# Arduino_DUE_X_V02d-2Layer.net
KiCad netlist of a schematic drawn in EAGLE
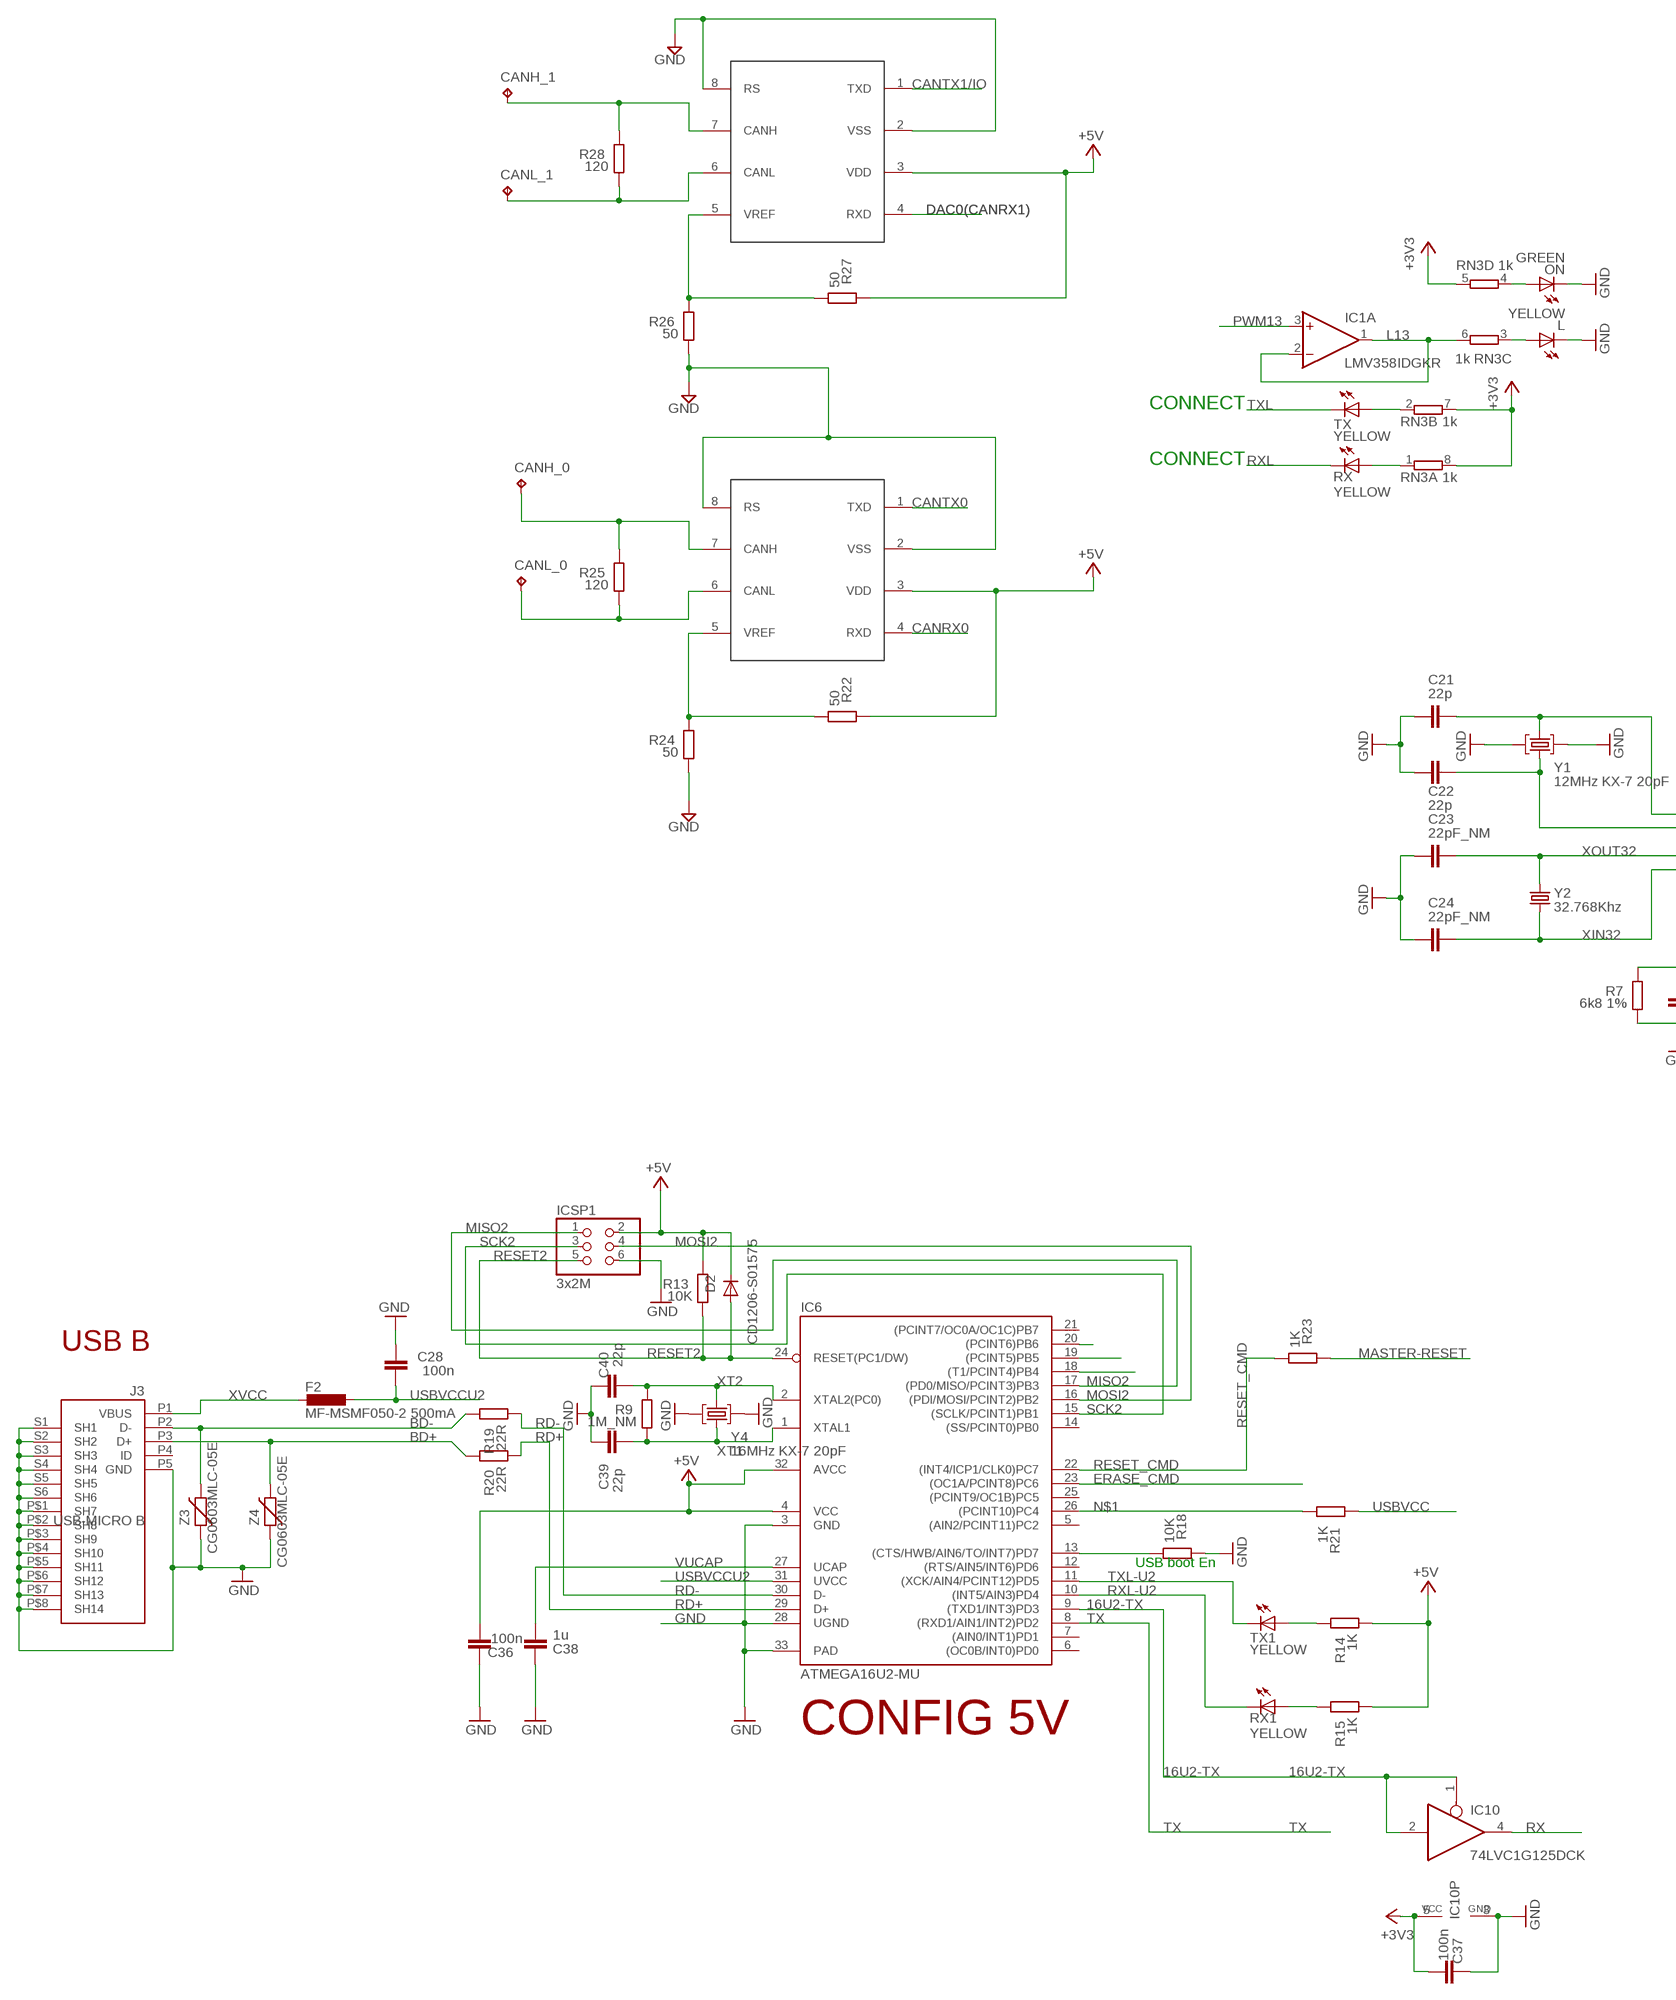
[diagram p0: schematic, sheet 1, part 1 of 2]
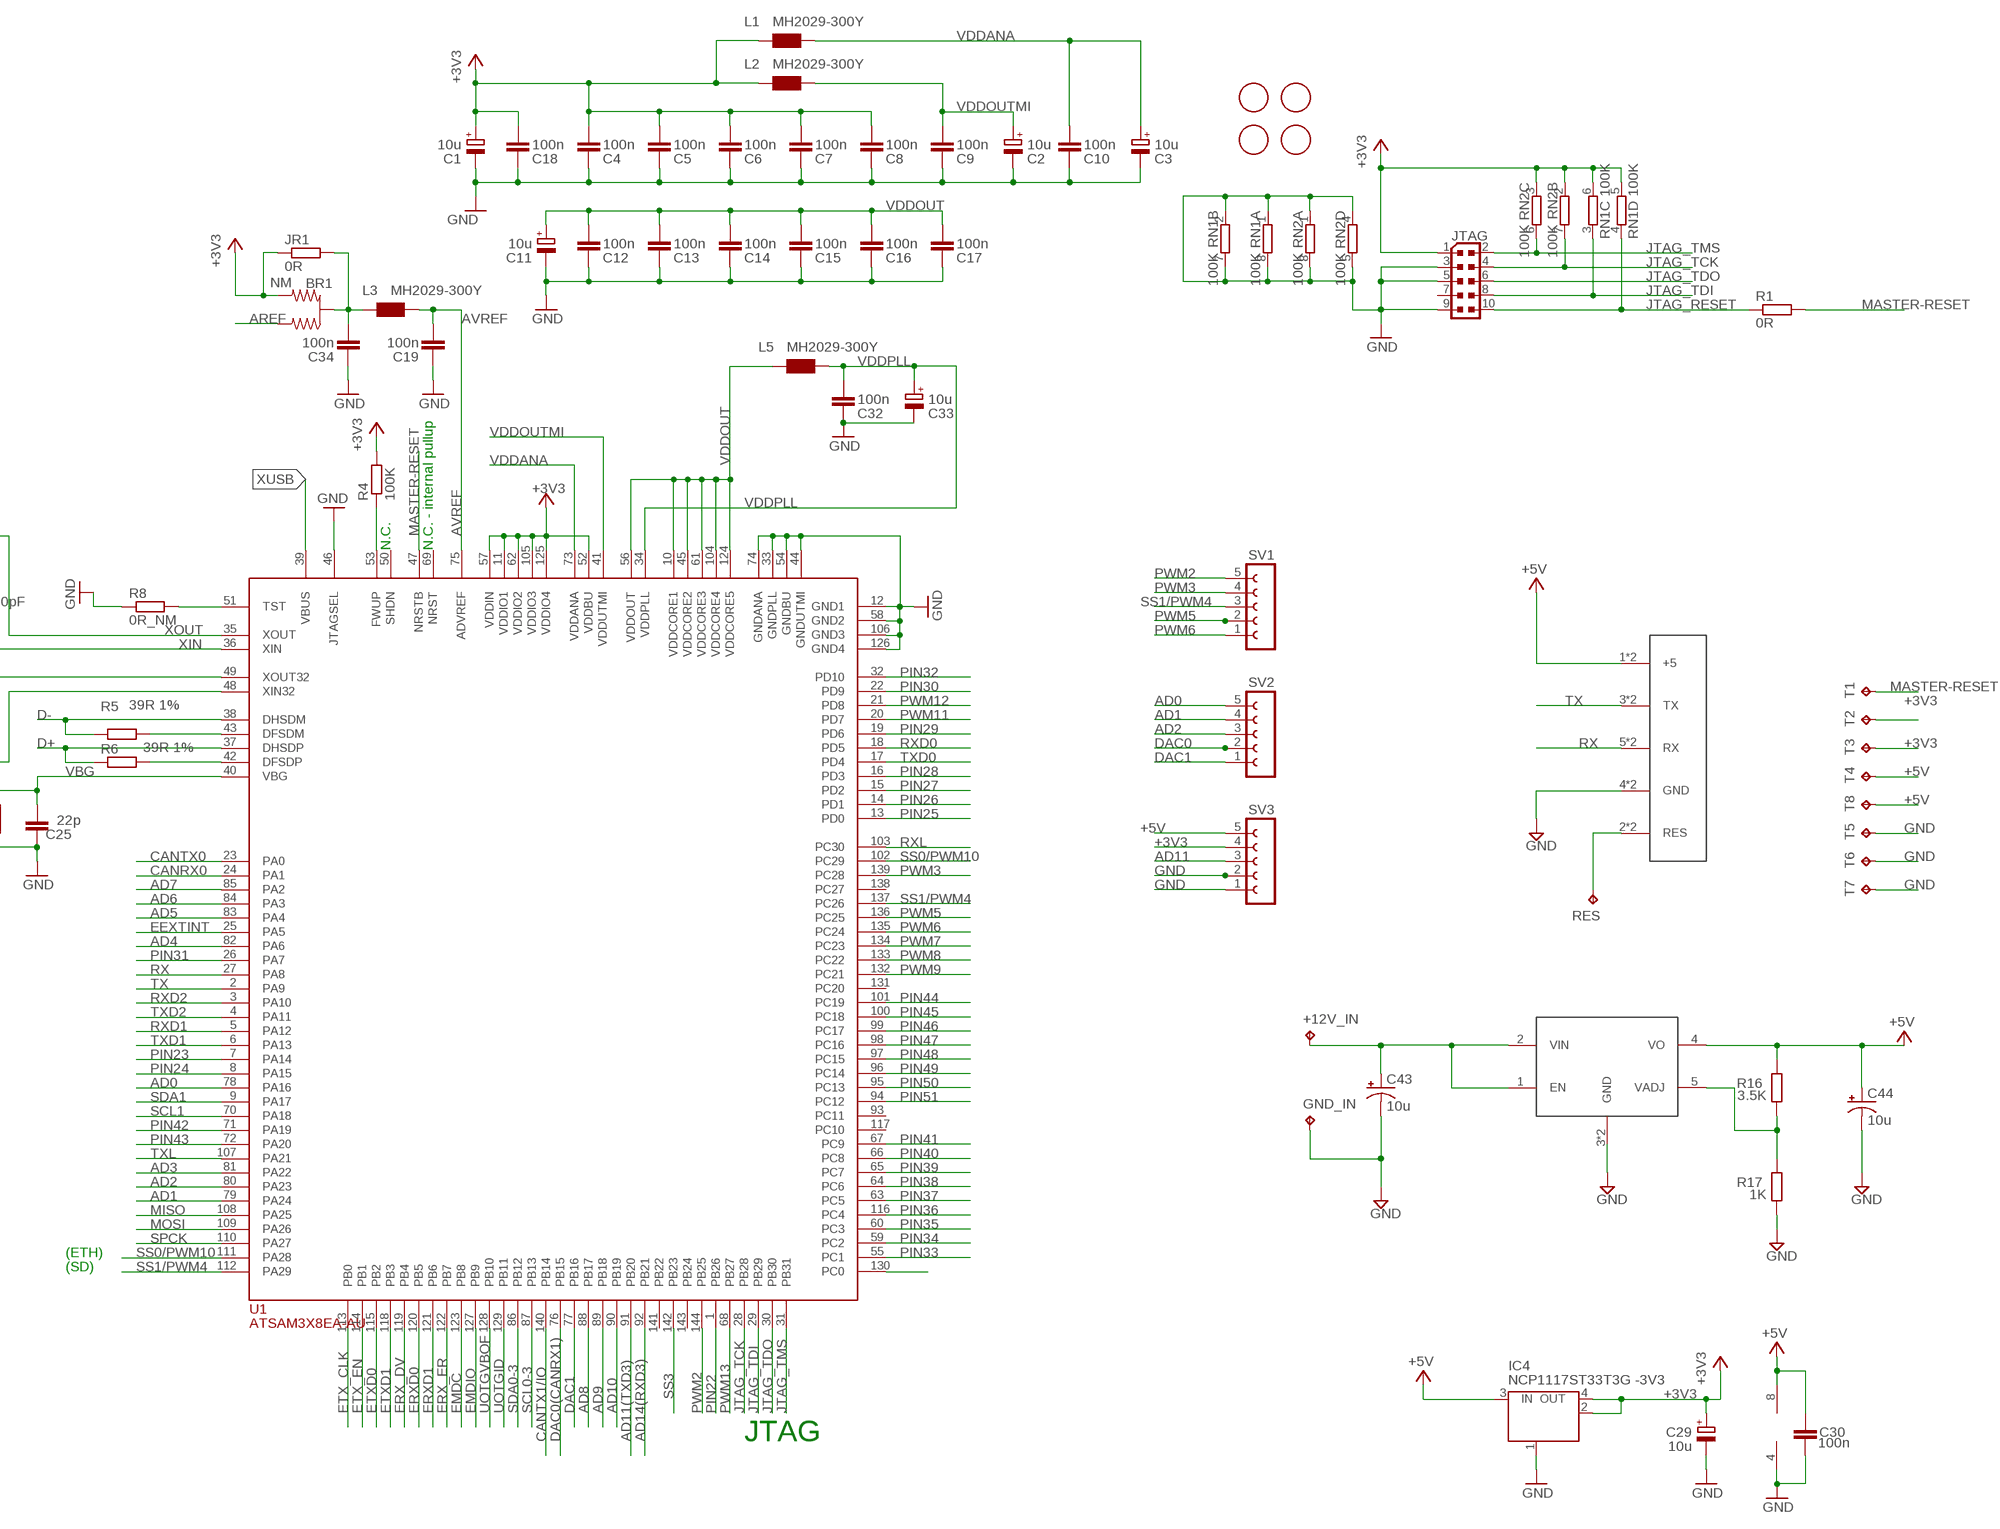
[diagram p1: schematic, sheet 1, part 2 of 2]

(export (version "E")
  (design (tool "Eeschema 10.0.6"))
  (components
    (comp (ref "+12V_IN")
      (value "TPPAD1-13")
      (footprint "eagle-import:P1-13")
      (libsource (lib "eagle-import") (part "TPPAD1-13"))
    )
    (comp (ref "BR1")
      (value "NM")
      (footprint "eagle-import:J0402")
      (libsource (lib "eagle-import") (part "J0402"))
    )
    (comp (ref "C1")
      (value "10u")
      (footprint "eagle-import:SMC_B")
      (libsource (lib "eagle-import") (part "CPOL-EUSMCB"))
    )
    (comp (ref "C2")
      (value "10u")
      (footprint "eagle-import:SMC_B")
      (libsource (lib "eagle-import") (part "CPOL-EUSMCB"))
    )
    (comp (ref "C3")
      (value "10u")
      (footprint "eagle-import:SMC_B")
      (libsource (lib "eagle-import") (part "CPOL-EUSMCB"))
    )
    (comp (ref "C4")
      (value "100n")
      (footprint "eagle-import:C0805")
      (libsource (lib "eagle-import") (part "C-EUC0805"))
    )
    (comp (ref "C5")
      (value "100n")
      (footprint "eagle-import:C0805")
      (libsource (lib "eagle-import") (part "C-EUC0805"))
    )
    (comp (ref "C6")
      (value "100n")
      (footprint "eagle-import:C0805")
      (libsource (lib "eagle-import") (part "C-EUC0805"))
    )
    (comp (ref "C7")
      (value "100n")
      (footprint "eagle-import:C0805")
      (libsource (lib "eagle-import") (part "C-EUC0805"))
    )
    (comp (ref "C8")
      (value "100n")
      (footprint "eagle-import:C0805")
      (libsource (lib "eagle-import") (part "C-EUC0805"))
    )
    (comp (ref "C9")
      (value "100n")
      (footprint "eagle-import:C0805")
      (libsource (lib "eagle-import") (part "C-EUC0805"))
    )
    (comp (ref "C10")
      (value "100n")
      (footprint "eagle-import:C0805")
      (libsource (lib "eagle-import") (part "C-EUC0805"))
    )
    (comp (ref "C11")
      (value "10u")
      (footprint "eagle-import:SMC_B")
      (libsource (lib "eagle-import") (part "CPOL-EUSMCB"))
    )
    (comp (ref "C12")
      (value "100n")
      (footprint "eagle-import:C0805")
      (libsource (lib "eagle-import") (part "C-EUC0805"))
    )
    (comp (ref "C13")
      (value "100n")
      (footprint "eagle-import:C0805")
      (libsource (lib "eagle-import") (part "C-EUC0805"))
    )
    (comp (ref "C14")
      (value "100n")
      (footprint "eagle-import:C0805")
      (libsource (lib "eagle-import") (part "C-EUC0805"))
    )
    (comp (ref "C15")
      (value "100n")
      (footprint "eagle-import:C0805")
      (libsource (lib "eagle-import") (part "C-EUC0805"))
    )
    (comp (ref "C16")
      (value "100n")
      (footprint "eagle-import:C0805")
      (libsource (lib "eagle-import") (part "C-EUC0805"))
    )
    (comp (ref "C17")
      (value "100n")
      (footprint "eagle-import:C0805")
      (libsource (lib "eagle-import") (part "C-EUC0805"))
    )
    (comp (ref "C18")
      (value "100n")
      (footprint "eagle-import:C0805")
      (libsource (lib "eagle-import") (part "C-EUC0805"))
    )
    (comp (ref "C19")
      (value "100n")
      (footprint "eagle-import:C0805")
      (libsource (lib "eagle-import") (part "C-EUC0805"))
    )
    (comp (ref "C21")
      (value "22p")
      (footprint "eagle-import:C0805")
      (libsource (lib "eagle-import") (part "C-EUC0805"))
    )
    (comp (ref "C22")
      (value "22p")
      (footprint "eagle-import:C0805")
      (libsource (lib "eagle-import") (part "C-EUC0805"))
    )
    (comp (ref "C23")
      (value "22pF_NM")
      (footprint "eagle-import:C0805")
      (libsource (lib "eagle-import") (part "C-EUC0805"))
    )
    (comp (ref "C24")
      (value "22pF_NM")
      (footprint "eagle-import:C0805")
      (libsource (lib "eagle-import") (part "C-EUC0805"))
    )
    (comp (ref "C25")
      (value "22p")
      (footprint "eagle-import:C0805")
      (libsource (lib "eagle-import") (part "C-EUC0805"))
    )
    (comp (ref "C28")
      (value "100n")
      (footprint "eagle-import:C0805")
      (libsource (lib "eagle-import") (part "C-EUC0805"))
    )
    (comp (ref "C29")
      (value "10u")
      (footprint "eagle-import:SMC_B")
      (libsource (lib "eagle-import") (part "CPOL-EUSMCB"))
    )
    (comp (ref "C30")
      (value "100n")
      (footprint "eagle-import:C0805")
      (libsource (lib "eagle-import") (part "C-EUC0805"))
    )
    (comp (ref "C32")
      (value "100n")
      (footprint "eagle-import:C0805")
      (libsource (lib "eagle-import") (part "C-EUC0805"))
    )
    (comp (ref "C33")
      (value "10u")
      (footprint "eagle-import:SMC_B")
      (libsource (lib "eagle-import") (part "CPOL-EUSMCB"))
    )
    (comp (ref "C34")
      (value "100n")
      (footprint "eagle-import:C0805")
      (libsource (lib "eagle-import") (part "C-EUC0805"))
    )
    (comp (ref "C36")
      (value "100n")
      (footprint "eagle-import:C0805")
      (libsource (lib "eagle-import") (part "C-EUC0805"))
    )
    (comp (ref "C37")
      (value "100n")
      (footprint "eagle-import:C0805")
      (libsource (lib "eagle-import") (part "C-EUC0805"))
    )
    (comp (ref "C38")
      (value "1u")
      (footprint "eagle-import:C0805")
      (libsource (lib "eagle-import") (part "C-EUC0805"))
    )
    (comp (ref "C39")
      (value "22p")
      (footprint "eagle-import:C0805")
      (libsource (lib "eagle-import") (part "C-EUC0805"))
    )
    (comp (ref "C40")
      (value "22p")
      (footprint "eagle-import:C0805")
      (libsource (lib "eagle-import") (part "C-EUC0805"))
    )
    (comp (ref "C43")
      (value "10u")
      (footprint "eagle-import:153CLV-0405")
      (libsource (lib "eagle-import") (part "CPOL-US153CLV-0405"))
    )
    (comp (ref "C44")
      (value "10u")
      (footprint "eagle-import:153CLV-0405")
      (libsource (lib "eagle-import") (part "CPOL-US153CLV-0405"))
    )
    (comp (ref "CANH_0")
      (value "TPPAD1-13")
      (footprint "eagle-import:P1-13")
      (libsource (lib "eagle-import") (part "TPPAD1-13"))
    )
    (comp (ref "CANH_1")
      (value "TPPAD1-13")
      (footprint "eagle-import:P1-13")
      (libsource (lib "eagle-import") (part "TPPAD1-13"))
    )
    (comp (ref "CANL_0")
      (value "TPPAD1-13")
      (footprint "eagle-import:P1-13")
      (libsource (lib "eagle-import") (part "TPPAD1-13"))
    )
    (comp (ref "CANL_1")
      (value "TPPAD1-13")
      (footprint "eagle-import:P1-13")
      (libsource (lib "eagle-import") (part "TPPAD1-13"))
    )
    (comp (ref "D2")
      (value "CD1206-S01575")
      (footprint "eagle-import:MINIMELF")
      (libsource (lib "eagle-import") (part "DIODE-MINIMELF"))
    )
    (comp (ref "F2")
      (value "MF-MSMF050-2 500mA")
      (footprint "eagle-import:L1812")
      (libsource (lib "eagle-import") (part "L-EUL1812"))
    )
    (comp (ref "FID1")
      (value "FIDUCIALMOUNT")
      (footprint "eagle-import:FIDUCIA-MOUNT")
      (libsource (lib "eagle-import") (part "FIDUCIALMOUNT"))
    )
    (comp (ref "FID2")
      (value "FIDUCIALMOUNT")
      (footprint "eagle-import:FIDUCIA-MOUNT")
      (libsource (lib "eagle-import") (part "FIDUCIALMOUNT"))
    )
    (comp (ref "FID3")
      (value "FIDUCIALMOUNT")
      (footprint "eagle-import:FIDUCIA-MOUNT")
      (libsource (lib "eagle-import") (part "FIDUCIALMOUNT"))
    )
    (comp (ref "FID4")
      (value "FIDUCIALMOUNT")
      (footprint "eagle-import:FIDUCIA-MOUNT")
      (libsource (lib "eagle-import") (part "FIDUCIALMOUNT"))
    )
    (comp (ref "GND_IN")
      (value "TPPAD1-13")
      (footprint "eagle-import:P1-13")
      (libsource (lib "eagle-import") (part "TPPAD1-13"))
    )
    (comp (ref "IC1")
      (value "LMV358IDGKR")
      (footprint "eagle-import:MSOP08")
      (libsource (lib "eagle-import") (part "LMV358?MMX"))
    )
    (comp (ref "IC4")
      (value "NCP1117ST33T3G -3V3")
      (footprint "eagle-import:SOT223")
      (libsource (lib "eagle-import") (part "MC33269ST-3.3T3"))
    )
    (comp (ref "IC6")
      (value "ATMEGA16U2-MU")
      (footprint "eagle-import:MLF32")
      (libsource (lib "eagle-import") (part "ATMEGA16U2-MU"))
    )
    (comp (ref "IC10")
      (value "74LVC1G125DCK")
      (footprint "eagle-import:SC70-5")
      (libsource (lib "eagle-import") (part "741G125DCKLVC"))
    )
    (comp (ref "ICSP1")
      (value "3x2M")
      (footprint "eagle-import:2X03")
      (libsource (lib "eagle-import") (part "PINHD-2X3"))
    )
    (comp (ref "J3")
      (value "USB-MICRO B")
      (footprint "eagle-import:CON2_USB_MICRO_B_AT")
      (libsource (lib "eagle-import") (part "MYCON2_USB-MINI-B"))
    )
    (comp (ref "JR1")
      (value "0R")
      (footprint "eagle-import:R0805")
      (libsource (lib "eagle-import") (part "R-EU_R0805"))
    )
    (comp (ref "JTAG")
      (value "PINHEAD_PINHD-2X5PASSO127")
      (footprint "eagle-import:PINHEAD_2X05_127")
      (libsource (lib "eagle-import") (part "PINHEAD_PINHD-2X5PASSO127"))
    )
    (comp (ref "L")
      (value "YELLOW")
      (footprint "eagle-import:CHIP-LED0805")
      (libsource (lib "eagle-import") (part "LEDCHIP-LED0805"))
    )
    (comp (ref "L1")
      (value "MH2029-300Y")
      (footprint "eagle-import:0805")
      (libsource (lib "eagle-import") (part "WE-CBF_0805"))
    )
    (comp (ref "L2")
      (value "MH2029-300Y")
      (footprint "eagle-import:0805")
      (libsource (lib "eagle-import") (part "WE-CBF_0805"))
    )
    (comp (ref "L3")
      (value "MH2029-300Y")
      (footprint "eagle-import:0805")
      (libsource (lib "eagle-import") (part "WE-CBF_0805"))
    )
    (comp (ref "L5")
      (value "MH2029-300Y")
      (footprint "eagle-import:0805")
      (libsource (lib "eagle-import") (part "WE-CBF_0805"))
    )
    (comp (ref "ON")
      (value "GREEN")
      (footprint "eagle-import:CHIP-LED0805")
      (libsource (lib "eagle-import") (part "LEDCHIP-LED0805"))
    )
    (comp (ref "R1")
      (value "0R")
      (footprint "eagle-import:R0805")
      (libsource (lib "eagle-import") (part "R-EU_R0805"))
    )
    (comp (ref "R4")
      (value "100K")
      (footprint "eagle-import:R0805")
      (libsource (lib "eagle-import") (part "R-EU_R0805"))
    )
    (comp (ref "R5")
      (value "39R 1%")
      (footprint "eagle-import:R0805")
      (libsource (lib "eagle-import") (part "R-EU_R0805"))
    )
    (comp (ref "R6")
      (value "39R 1%")
      (footprint "eagle-import:R0805")
      (libsource (lib "eagle-import") (part "R-EU_R0805"))
    )
    (comp (ref "R7")
      (value "6k8 1%")
      (footprint "eagle-import:R0805")
      (libsource (lib "eagle-import") (part "R-EU_R0805"))
    )
    (comp (ref "R8")
      (value "0R_NM")
      (footprint "eagle-import:R0805")
      (libsource (lib "eagle-import") (part "R-EU_R0805"))
    )
    (comp (ref "R9")
      (value "1M_NM")
      (footprint "eagle-import:R0805")
      (libsource (lib "eagle-import") (part "R-EU_R0805"))
    )
    (comp (ref "R13")
      (value "10K")
      (footprint "eagle-import:R0805")
      (libsource (lib "eagle-import") (part "R-EU_R0805"))
    )
    (comp (ref "R14")
      (value "1K")
      (footprint "eagle-import:R0805")
      (libsource (lib "eagle-import") (part "R-EU_R0805"))
    )
    (comp (ref "R15")
      (value "1K")
      (footprint "eagle-import:R0805")
      (libsource (lib "eagle-import") (part "R-EU_R0805"))
    )
    (comp (ref "R16")
      (value "3.5K")
      (footprint "eagle-import:R0805")
      (libsource (lib "eagle-import") (part "R-EU_R0805"))
    )
    (comp (ref "R17")
      (value "1K")
      (footprint "eagle-import:R0805")
      (libsource (lib "eagle-import") (part "R-EU_R0805"))
    )
    (comp (ref "R18")
      (value "10K")
      (footprint "eagle-import:R0805")
      (libsource (lib "eagle-import") (part "R-EU_R0805"))
    )
    (comp (ref "R19")
      (value "22R")
      (footprint "eagle-import:R0805")
      (libsource (lib "eagle-import") (part "R-EU_R0805"))
    )
    (comp (ref "R20")
      (value "22R")
      (footprint "eagle-import:R0805")
      (libsource (lib "eagle-import") (part "R-EU_R0805"))
    )
    (comp (ref "R21")
      (value "1K")
      (footprint "eagle-import:R0805")
      (libsource (lib "eagle-import") (part "R-EU_R0805"))
    )
    (comp (ref "R22")
      (value "50")
      (footprint "eagle-import:R0805")
      (libsource (lib "eagle-import") (part "R-EU_R0805"))
    )
    (comp (ref "R23")
      (value "1K")
      (footprint "eagle-import:R0805")
      (libsource (lib "eagle-import") (part "R-EU_R0805"))
    )
    (comp (ref "R24")
      (value "50")
      (footprint "eagle-import:R0805")
      (libsource (lib "eagle-import") (part "R-EU_R0805"))
    )
    (comp (ref "R25")
      (value "120")
      (footprint "eagle-import:R0805")
      (libsource (lib "eagle-import") (part "R-EU_R0805"))
    )
    (comp (ref "R26")
      (value "50")
      (footprint "eagle-import:R0805")
      (libsource (lib "eagle-import") (part "R-EU_R0805"))
    )
    (comp (ref "R27")
      (value "50")
      (footprint "eagle-import:R0805")
      (libsource (lib "eagle-import") (part "R-EU_R0805"))
    )
    (comp (ref "R28")
      (value "120")
      (footprint "eagle-import:R0805")
      (libsource (lib "eagle-import") (part "R-EU_R0805"))
    )
    (comp (ref "RES")
      (value "TPB1,27")
      (footprint "eagle-import:B1,27")
      (libsource (lib "eagle-import") (part "TPB1,27"))
    )
    (comp (ref "RN1")
      (value "100K")
      (footprint "eagle-import:CAT16")
      (libsource (lib "eagle-import") (part "4R-NCAT16"))
    )
    (comp (ref "RN2")
      (value "100K")
      (footprint "eagle-import:CAT16")
      (libsource (lib "eagle-import") (part "4R-NCAT16"))
    )
    (comp (ref "RN3")
      (value "1k")
      (footprint "eagle-import:CAY16")
      (libsource (lib "eagle-import") (part "4R-NCAY16"))
    )
    (comp (ref "RX")
      (value "YELLOW")
      (footprint "eagle-import:CHIP-LED0805")
      (libsource (lib "eagle-import") (part "LEDCHIP-LED0805"))
    )
    (comp (ref "RX1")
      (value "YELLOW")
      (footprint "eagle-import:CHIP-LED0805")
      (libsource (lib "eagle-import") (part "LEDCHIP-LED0805"))
    )
    (comp (ref "SV1")
      (value "FE05-1")
      (footprint "eagle-import:FE05-1")
      (libsource (lib "eagle-import") (part "FE05-1"))
    )
    (comp (ref "SV2")
      (value "FE05-1")
      (footprint "eagle-import:FE05-1")
      (libsource (lib "eagle-import") (part "FE05-1"))
    )
    (comp (ref "SV3")
      (value "FE05-1")
      (footprint "eagle-import:FE05-1")
      (libsource (lib "eagle-import") (part "FE05-1"))
    )
    (comp (ref "T1")
      (value "TPB1,27")
      (footprint "eagle-import:B1,27")
      (libsource (lib "eagle-import") (part "TPB1,27"))
    )
    (comp (ref "T2")
      (value "TPTP10R")
      (footprint "eagle-import:TP10R")
      (libsource (lib "eagle-import") (part "TPTP10R"))
    )
    (comp (ref "T3")
      (value "TPB1,27")
      (footprint "eagle-import:B1,27")
      (libsource (lib "eagle-import") (part "TPB1,27"))
    )
    (comp (ref "T4")
      (value "TPB1,27")
      (footprint "eagle-import:B1,27")
      (libsource (lib "eagle-import") (part "TPB1,27"))
    )
    (comp (ref "T5")
      (value "TPB1,27")
      (footprint "eagle-import:B1,27")
      (libsource (lib "eagle-import") (part "TPB1,27"))
    )
    (comp (ref "T6")
      (value "TPTP20SQ")
      (footprint "eagle-import:TP20SQ")
      (libsource (lib "eagle-import") (part "TPTP20SQ"))
    )
    (comp (ref "T7")
      (value "TPTP20SQ")
      (footprint "eagle-import:TP20SQ")
      (libsource (lib "eagle-import") (part "TPTP20SQ"))
    )
    (comp (ref "T8")
      (value "TPB1,27")
      (footprint "eagle-import:B1,27")
      (libsource (lib "eagle-import") (part "TPB1,27"))
    )
    (comp (ref "TX")
      (value "YELLOW")
      (footprint "eagle-import:CHIP-LED0805")
      (libsource (lib "eagle-import") (part "LEDCHIP-LED0805"))
    )
    (comp (ref "TX1")
      (value "YELLOW")
      (footprint "eagle-import:CHIP-LED0805")
      (libsource (lib "eagle-import") (part "LEDCHIP-LED0805"))
    )
    (comp (ref "U$1")
      (value "TLF1963TBATMA1")
      (footprint "eagle-import:DPAK")
      (libsource (lib "eagle-import") (part "TLF1963"))
    )
    (comp (ref "U1")
      (value "ATSAM3X8EA-AU")
      (footprint "eagle-import:LQFP144")
      (libsource (lib "eagle-import") (part "ATSAM3X/AAU"))
    )
    (comp (ref "U2")
      (value "MCP2551")
      (footprint "eagle-import:SOIC8")
      (libsource (lib "eagle-import") (part "MCP2551"))
    )
    (comp (ref "U3")
      (value "LCD_DISPLAY")
      (footprint "eagle-import:FE05-2")
      (libsource (lib "eagle-import") (part "LCD_DISPLAY"))
    )
    (comp (ref "U4")
      (value "MCP2551")
      (footprint "eagle-import:SOIC8")
      (libsource (lib "eagle-import") (part "MCP2551"))
    )
    (comp (ref "Y1")
      (value "12MHz KX-7 20pF")
      (footprint "eagle-import:CRYSTAL-3.2-2.5")
      (libsource (lib "eagle-import") (part "CRYSTAL-3.2-2.5"))
    )
    (comp (ref "Y2")
      (value "32.768Khz")
      (footprint "eagle-import:RESONATOR_EPSON_FC_145")
      (libsource (lib "eagle-import") (part "RESONATOR_EPSON_FC_145"))
    )
    (comp (ref "Y4")
      (value "16MHz KX-7 20pF")
      (footprint "eagle-import:CRYSTAL-3.2-2.5")
      (libsource (lib "eagle-import") (part "CRYSTAL-3.2-2.5"))
    )
    (comp (ref "Z3")
      (value "CG0603MLC-05E")
      (footprint "eagle-import:CT_CN0805")
      (libsource (lib "eagle-import") (part "VARISTORCN0805"))
    )
    (comp (ref "Z4")
      (value "CG0603MLC-05E")
      (footprint "eagle-import:CT_CN0805")
      (libsource (lib "eagle-import") (part "VARISTORCN0805"))
    )
  )
  (nets
    (net (code "1") (name "+3V3") (class "Default")
      (node (ref "BR1") (pin "3") (pinfunction "2_3") (pintype "passive"))
      (node (ref "C1") (pin "+") (pinfunction "+_+") (pintype "passive"))
      (node (ref "C18") (pin "2") (pinfunction "2_2") (pintype "passive"))
      (node (ref "C29") (pin "+") (pinfunction "+_+") (pintype "passive"))
      (node (ref "C37") (pin "1") (pinfunction "1_1") (pintype "passive"))
      (node (ref "C4") (pin "2") (pinfunction "2_2") (pintype "passive"))
      (node (ref "C5") (pin "2") (pinfunction "2_2") (pintype "passive"))
      (node (ref "C6") (pin "2") (pinfunction "2_2") (pintype "passive"))
      (node (ref "C7") (pin "2") (pinfunction "2_2") (pintype "passive"))
      (node (ref "C8") (pin "2") (pinfunction "2_2") (pintype "passive"))
      (node (ref "IC10") (pin "5") (pinfunction "VCC_5") (pintype "power_in"))
      (node (ref "IC4") (pin "2") (pinfunction "OUT_2") (pintype "passive"))
      (node (ref "IC4") (pin "4") (pinfunction "OUT_4") (pintype "passive"))
      (node (ref "JR1") (pin "1") (pinfunction "1_1") (pintype "passive"))
      (node (ref "JTAG") (pin "1") (pinfunction "1_1") (pintype "passive"))
      (node (ref "L1") (pin "1") (pinfunction "1_1") (pintype "passive"))
      (node (ref "L2") (pin "1") (pinfunction "1_1") (pintype "passive"))
      (node (ref "R4") (pin "2") (pinfunction "2_2") (pintype "passive"))
      (node (ref "RN1") (pin "5") (pinfunction "2_5") (pintype "passive"))
      (node (ref "RN1") (pin "6") (pinfunction "2_6") (pintype "passive"))
      (node (ref "RN2") (pin "2") (pinfunction "1_2") (pintype "passive"))
      (node (ref "RN2") (pin "3") (pinfunction "1_3") (pintype "passive"))
      (node (ref "RN3") (pin "5") (pinfunction "2_5") (pintype "passive"))
      (node (ref "RN3") (pin "7") (pinfunction "2_7") (pintype "passive"))
      (node (ref "RN3") (pin "8") (pinfunction "2_8") (pintype "passive"))
      (node (ref "SV3") (pin "4") (pinfunction "4_4") (pintype "passive"))
      (node (ref "T2") (pin "TP") (pinfunction "TP_TP") (pintype "input"))
      (node (ref "T3") (pin "TP") (pinfunction "TP_TP") (pintype "input"))
      (node (ref "U1") (pin "105") (pinfunction "VDDIO3_105") (pintype "power_in"))
      (node (ref "U1") (pin "11") (pinfunction "VDDIO1_11") (pintype "power_in"))
      (node (ref "U1") (pin "125") (pinfunction "VDDIO4_125") (pintype "power_in"))
      (node (ref "U1") (pin "52") (pinfunction "VDDBU_52") (pintype "power_in"))
      (node (ref "U1") (pin "57") (pinfunction "VDDIN_57") (pintype "power_in"))
      (node (ref "U1") (pin "62") (pinfunction "VDDIO2_62") (pintype "power_in"))
    )
    (net (code "2") (name "+5V") (class "Default")
      (node (ref "C30") (pin "2") (pinfunction "2_2") (pintype "passive"))
      (node (ref "C36") (pin "1") (pinfunction "1_1") (pintype "passive"))
      (node (ref "C44") (pin "+") (pinfunction "+_+") (pintype "passive"))
      (node (ref "D2") (pin "C") (pinfunction "C_C") (pintype "passive"))
      (node (ref "IC1") (pin "8") (pinfunction "V+_8") (pintype "power_in"))
      (node (ref "IC4") (pin "3") (pinfunction "IN_3") (pintype "input"))
      (node (ref "IC6") (pin "32") (pinfunction "AVCC_32") (pintype "power_in"))
      (node (ref "IC6") (pin "4") (pinfunction "VCC_4") (pintype "power_in"))
      (node (ref "ICSP1") (pin "2") (pinfunction "2_2") (pintype "passive"))
      (node (ref "R13") (pin "2") (pinfunction "2_2") (pintype "passive"))
      (node (ref "R14") (pin "1") (pinfunction "1_1") (pintype "passive"))
      (node (ref "R15") (pin "1") (pinfunction "1_1") (pintype "passive"))
      (node (ref "R16") (pin "2") (pinfunction "2_2") (pintype "passive"))
      (node (ref "R22") (pin "2") (pinfunction "2_2") (pintype "passive"))
      (node (ref "R27") (pin "2") (pinfunction "2_2") (pintype "passive"))
      (node (ref "SV3") (pin "5") (pinfunction "5_5") (pintype "passive"))
      (node (ref "T4") (pin "TP") (pinfunction "TP_TP") (pintype "input"))
      (node (ref "T8") (pin "TP") (pinfunction "TP_TP") (pintype "input"))
      (node (ref "U$1") (pin "4") (pinfunction "VO_4") (pintype "bidirectional"))
      (node (ref "U2") (pin "3") (pinfunction "VDD_3") (pintype "bidirectional"))
      (node (ref "U3") (pin "1") (pinfunction "+5_1") (pintype "bidirectional"))
      (node (ref "U3") (pin "10") (pinfunction "+5_10") (pintype "bidirectional"))
      (node (ref "U4") (pin "3") (pinfunction "VDD_3") (pintype "bidirectional"))
    )
    (net (code "3") (name "/16U2-TX") (class "Default")
      (node (ref "IC10") (pin "1") (pinfunction "OE_1") (pintype "input"))
      (node (ref "IC10") (pin "2") (pinfunction "I_2") (pintype "input"))
      (node (ref "IC6") (pin "9") (pinfunction "(TXD1/INT3)PD3_9") (pintype "bidirectional"))
    )
    (net (code "4") (name "/AD0") (class "Default")
      (node (ref "SV2") (pin "5") (pinfunction "5_5") (pintype "passive"))
      (node (ref "U1") (pin "78") (pinfunction "PA16_78") (pintype "bidirectional"))
    )
    (net (code "5") (name "/AD1") (class "Default")
      (node (ref "SV2") (pin "4") (pinfunction "4_4") (pintype "passive"))
      (node (ref "U1") (pin "79") (pinfunction "PA24_79") (pintype "bidirectional"))
    )
    (net (code "6") (name "/AD2") (class "Default")
      (node (ref "SV2") (pin "3") (pinfunction "3_3") (pintype "passive"))
      (node (ref "U1") (pin "80") (pinfunction "PA23_80") (pintype "bidirectional"))
    )
    (net (code "7") (name "/AD3") (class "Default")
      (node (ref "U1") (pin "81") (pinfunction "PA22_81") (pintype "bidirectional"))
    )
    (net (code "8") (name "/AD4") (class "Default")
      (node (ref "U1") (pin "82") (pinfunction "PA6_82") (pintype "bidirectional"))
    )
    (net (code "9") (name "/AD5") (class "Default")
      (node (ref "U1") (pin "83") (pinfunction "PA4_83") (pintype "bidirectional"))
    )
    (net (code "10") (name "/AD6") (class "Default")
      (node (ref "U1") (pin "84") (pinfunction "PA3_84") (pintype "bidirectional"))
    )
    (net (code "11") (name "/AD7") (class "Default")
      (node (ref "U1") (pin "85") (pinfunction "PA2_85") (pintype "bidirectional"))
    )
    (net (code "12") (name "/AD8") (class "Default")
      (node (ref "U1") (pin "88") (pinfunction "PB17_88") (pintype "bidirectional"))
    )
    (net (code "13") (name "/AD9") (class "Default")
      (node (ref "U1") (pin "89") (pinfunction "PB18_89") (pintype "bidirectional"))
    )
    (net (code "14") (name "/AD10") (class "Default")
      (node (ref "U1") (pin "90") (pinfunction "PB19_90") (pintype "bidirectional"))
    )
    (net (code "15") (name "/AD11") (class "Default")
      (node (ref "SV3") (pin "3") (pinfunction "3_3") (pintype "passive"))
    )
    (net (code "16") (name "/AD11(TXD3)") (class "Default")
      (node (ref "U1") (pin "91") (pinfunction "PB20_91") (pintype "bidirectional"))
    )
    (net (code "17") (name "/AD14(RXD3)") (class "Default")
      (node (ref "U1") (pin "92") (pinfunction "PB21_92") (pintype "bidirectional"))
    )
    (net (code "18") (name "/AREF") (class "Default")
      (node (ref "BR1") (pin "1") (pinfunction "1_1") (pintype "passive"))
    )
    (net (code "19") (name "/AVREF") (class "Default")
      (node (ref "C19") (pin "2") (pinfunction "2_2") (pintype "passive"))
      (node (ref "L3") (pin "2") (pinfunction "2_2") (pintype "passive"))
      (node (ref "U1") (pin "75") (pinfunction "ADVREF_75") (pintype "power_in"))
    )
    (net (code "20") (name "/BD+") (class "Default")
      (node (ref "J3") (pin "P3") (pinfunction "D+_P3") (pintype "bidirectional"))
      (node (ref "R20") (pin "2") (pinfunction "2_2") (pintype "passive"))
      (node (ref "Z4") (pin "2") (pinfunction "2_2") (pintype "passive"))
    )
    (net (code "21") (name "/BD-") (class "Default")
      (node (ref "J3") (pin "P2") (pinfunction "D-_P2") (pintype "bidirectional"))
      (node (ref "R19") (pin "2") (pinfunction "2_2") (pintype "passive"))
      (node (ref "Z3") (pin "2") (pinfunction "2_2") (pintype "passive"))
    )
    (net (code "22") (name "/CANRX0") (class "Default")
      (node (ref "U1") (pin "24") (pinfunction "PA1_24") (pintype "bidirectional"))
      (node (ref "U4") (pin "4") (pinfunction "RXD_4") (pintype "bidirectional"))
    )
    (net (code "23") (name "/CANTX0") (class "Default")
      (node (ref "U1") (pin "23") (pinfunction "PA0_23") (pintype "bidirectional"))
      (node (ref "U4") (pin "1") (pinfunction "TXD_1") (pintype "bidirectional"))
    )
    (net (code "24") (name "/CANTX1{slash}IO") (class "Default")
      (node (ref "U1") (pin "140") (pinfunction "PB14_140") (pintype "bidirectional"))
      (node (ref "U2") (pin "1") (pinfunction "TXD_1") (pintype "bidirectional"))
    )
    (net (code "25") (name "/D+") (class "Default")
      (node (ref "R6") (pin "1") (pinfunction "1_1") (pintype "passive"))
      (node (ref "U1") (pin "37") (pinfunction "DHSDP_37") (pintype "bidirectional"))
    )
    (net (code "26") (name "/D-") (class "Default")
      (node (ref "R5") (pin "1") (pinfunction "1_1") (pintype "passive"))
      (node (ref "U1") (pin "38") (pinfunction "DHSDM_38") (pintype "bidirectional"))
    )
    (net (code "27") (name "/DAC0") (class "Default")
      (node (ref "SV2") (pin "2") (pinfunction "2_2") (pintype "passive"))
    )
    (net (code "28") (name "/DAC0(CANRX1)") (class "Default")
      (node (ref "U1") (pin "76") (pinfunction "PB15_76") (pintype "bidirectional"))
      (node (ref "U2") (pin "4") (pinfunction "RXD_4") (pintype "bidirectional"))
    )
    (net (code "29") (name "/DAC1") (class "Default")
      (node (ref "SV2") (pin "1") (pinfunction "1_1") (pintype "passive"))
      (node (ref "U1") (pin "77") (pinfunction "PB16_77") (pintype "bidirectional"))
    )
    (net (code "30") (name "/EEXTINT") (class "Default")
      (node (ref "U1") (pin "25") (pinfunction "PA5_25") (pintype "bidirectional"))
    )
    (net (code "31") (name "/EMDC") (class "Default")
      (node (ref "U1") (pin "123") (pinfunction "PB8_123") (pintype "bidirectional"))
    )
    (net (code "32") (name "/EMDIO") (class "Default")
      (node (ref "U1") (pin "127") (pinfunction "PB9_127") (pintype "bidirectional"))
    )
    (net (code "33") (name "/ERASE_CMD") (class "Default")
      (node (ref "IC6") (pin "23") (pinfunction "(OC1A/PCINT8)PC6_23") (pintype "bidirectional"))
    )
    (net (code "34") (name "/ERXD0") (class "Default")
      (node (ref "U1") (pin "120") (pinfunction "PB5_120") (pintype "bidirectional"))
    )
    (net (code "35") (name "/ERXD1") (class "Default")
      (node (ref "U1") (pin "121") (pinfunction "PB6_121") (pintype "bidirectional"))
    )
    (net (code "36") (name "/ERX_DV") (class "Default")
      (node (ref "U1") (pin "119") (pinfunction "PB4_119") (pintype "bidirectional"))
    )
    (net (code "37") (name "/ERX_ER") (class "Default")
      (node (ref "U1") (pin "122") (pinfunction "PB7_122") (pintype "bidirectional"))
    )
    (net (code "38") (name "/ETXD0") (class "Default")
      (node (ref "U1") (pin "115") (pinfunction "PB2_115") (pintype "bidirectional"))
    )
    (net (code "39") (name "/ETXD1") (class "Default")
      (node (ref "U1") (pin "118") (pinfunction "PB3_118") (pintype "bidirectional"))
    )
    (net (code "40") (name "/ETX_CLK") (class "Default")
      (node (ref "U1") (pin "113") (pinfunction "PB0_113") (pintype "bidirectional"))
    )
    (net (code "41") (name "/ETX_EN") (class "Default")
      (node (ref "U1") (pin "114") (pinfunction "PB1_114") (pintype "bidirectional"))
    )
    (net (code "42") (name "/JTAG_RESET") (class "Default")
      (node (ref "JTAG") (pin "10") (pinfunction "10_10") (pintype "passive"))
      (node (ref "R1") (pin "1") (pinfunction "1_1") (pintype "passive"))
      (node (ref "RN1") (pin "4") (pinfunction "1_4") (pintype "passive"))
    )
    (net (code "43") (name "/JTAG_TCK") (class "Default")
      (node (ref "JTAG") (pin "4") (pinfunction "4_4") (pintype "passive"))
      (node (ref "RN2") (pin "7") (pinfunction "2_7") (pintype "passive"))
      (node (ref "U1") (pin "28") (pinfunction "PB28_28") (pintype "bidirectional"))
    )
    (net (code "44") (name "/JTAG_TDI") (class "Default")
      (node (ref "JTAG") (pin "8") (pinfunction "8_8") (pintype "passive"))
      (node (ref "RN1") (pin "3") (pinfunction "1_3") (pintype "passive"))
      (node (ref "U1") (pin "29") (pinfunction "PB29_29") (pintype "bidirectional"))
    )
    (net (code "45") (name "/JTAG_TDO") (class "Default")
      (node (ref "JTAG") (pin "6") (pinfunction "6_6") (pintype "passive"))
      (node (ref "U1") (pin "30") (pinfunction "PB30_30") (pintype "bidirectional"))
    )
    (net (code "46") (name "/JTAG_TMS") (class "Default")
      (node (ref "JTAG") (pin "2") (pinfunction "2_2") (pintype "passive"))
      (node (ref "RN2") (pin "6") (pinfunction "2_6") (pintype "passive"))
      (node (ref "U1") (pin "31") (pinfunction "PB31_31") (pintype "bidirectional"))
    )
    (net (code "47") (name "/L13") (class "Default")
      (node (ref "IC1") (pin "1") (pinfunction "OUT_1") (pintype "output"))
      (node (ref "IC1") (pin "2") (pinfunction "-IN_2") (pintype "input"))
      (node (ref "RN3") (pin "6") (pinfunction "2_6") (pintype "passive"))
    )
    (net (code "48") (name "/MASTER-RESET") (class "Default")
      (node (ref "R1") (pin "2") (pinfunction "2_2") (pintype "passive"))
      (node (ref "R23") (pin "2") (pinfunction "2_2") (pintype "passive"))
      (node (ref "T1") (pin "TP") (pinfunction "TP_TP") (pintype "input"))
      (node (ref "U1") (pin "47") (pinfunction "NRSTB_47") (pintype "input"))
    )
    (net (code "49") (name "/MISO") (class "Default")
      (node (ref "U1") (pin "108") (pinfunction "PA25_108") (pintype "bidirectional"))
    )
    (net (code "50") (name "/MISO2") (class "Default")
      (node (ref "IC6") (pin "17") (pinfunction "(PD0/MISO/PCINT3)PB3_17") (pintype "bidirectional"))
      (node (ref "ICSP1") (pin "1") (pinfunction "1_1") (pintype "passive"))
    )
    (net (code "51") (name "/MOSI") (class "Default")
      (node (ref "U1") (pin "109") (pinfunction "PA26_109") (pintype "bidirectional"))
    )
    (net (code "52") (name "/MOSI2") (class "Default")
      (node (ref "IC6") (pin "16") (pinfunction "(PDI/MOSI/PCINT2)PB2_16") (pintype "bidirectional"))
      (node (ref "ICSP1") (pin "4") (pinfunction "4_4") (pintype "passive"))
    )
    (net (code "53") (name "/N$1") (class "Default")
      (node (ref "IC6") (pin "26") (pinfunction "(PCINT10)PC4_26") (pintype "bidirectional"))
      (node (ref "R21") (pin "1") (pinfunction "1_1") (pintype "passive"))
    )
    (net (code "54") (name "/PIN22") (class "Default")
      (node (ref "U1") (pin "1") (pinfunction "PB26_1") (pintype "bidirectional"))
    )
    (net (code "55") (name "/PIN23") (class "Default")
      (node (ref "U1") (pin "7") (pinfunction "PA14_7") (pintype "bidirectional"))
    )
    (net (code "56") (name "/PIN24") (class "Default")
      (node (ref "U1") (pin "8") (pinfunction "PA15_8") (pintype "bidirectional"))
    )
    (net (code "57") (name "/PIN25") (class "Default")
      (node (ref "U1") (pin "13") (pinfunction "PD0_13") (pintype "bidirectional"))
    )
    (net (code "58") (name "/PIN26") (class "Default")
      (node (ref "U1") (pin "14") (pinfunction "PD1_14") (pintype "bidirectional"))
    )
    (net (code "59") (name "/PIN27") (class "Default")
      (node (ref "U1") (pin "15") (pinfunction "PD2_15") (pintype "bidirectional"))
    )
    (net (code "60") (name "/PIN28") (class "Default")
      (node (ref "U1") (pin "16") (pinfunction "PD3_16") (pintype "bidirectional"))
    )
    (net (code "61") (name "/PIN29") (class "Default")
      (node (ref "U1") (pin "19") (pinfunction "PD6_19") (pintype "bidirectional"))
    )
    (net (code "62") (name "/PIN30") (class "Default")
      (node (ref "U1") (pin "22") (pinfunction "PD9_22") (pintype "bidirectional"))
    )
    (net (code "63") (name "/PIN31") (class "Default")
      (node (ref "U1") (pin "26") (pinfunction "PA7_26") (pintype "bidirectional"))
    )
    (net (code "64") (name "/PIN32") (class "Default")
      (node (ref "U1") (pin "32") (pinfunction "PD10_32") (pintype "bidirectional"))
    )
    (net (code "65") (name "/PIN33") (class "Default")
      (node (ref "U1") (pin "55") (pinfunction "PC1_55") (pintype "bidirectional"))
    )
    (net (code "66") (name "/PIN34") (class "Default")
      (node (ref "U1") (pin "59") (pinfunction "PC2_59") (pintype "bidirectional"))
    )
    (net (code "67") (name "/PIN35") (class "Default")
      (node (ref "U1") (pin "60") (pinfunction "PC3_60") (pintype "bidirectional"))
    )
    (net (code "68") (name "/PIN36") (class "Default")
      (node (ref "U1") (pin "116") (pinfunction "PC4_116") (pintype "bidirectional"))
    )
    (net (code "69") (name "/PIN37") (class "Default")
      (node (ref "U1") (pin "63") (pinfunction "PC5_63") (pintype "bidirectional"))
    )
    (net (code "70") (name "/PIN38") (class "Default")
      (node (ref "U1") (pin "64") (pinfunction "PC6_64") (pintype "bidirectional"))
    )
    (net (code "71") (name "/PIN39") (class "Default")
      (node (ref "U1") (pin "65") (pinfunction "PC7_65") (pintype "bidirectional"))
    )
    (net (code "72") (name "/PIN40") (class "Default")
      (node (ref "U1") (pin "66") (pinfunction "PC8_66") (pintype "bidirectional"))
    )
    (net (code "73") (name "/PIN41") (class "Default")
      (node (ref "U1") (pin "67") (pinfunction "PC9_67") (pintype "bidirectional"))
    )
    (net (code "74") (name "/PIN42") (class "Default")
      (node (ref "U1") (pin "71") (pinfunction "PA19_71") (pintype "bidirectional"))
    )
    (net (code "75") (name "/PIN43") (class "Default")
      (node (ref "U1") (pin "72") (pinfunction "PA20_72") (pintype "bidirectional"))
    )
    (net (code "76") (name "/PIN44") (class "Default")
      (node (ref "U1") (pin "101") (pinfunction "PC19_101") (pintype "bidirectional"))
    )
    (net (code "77") (name "/PIN45") (class "Default")
      (node (ref "U1") (pin "100") (pinfunction "PC18_100") (pintype "bidirectional"))
    )
    (net (code "78") (name "/PIN46") (class "Default")
      (node (ref "U1") (pin "99") (pinfunction "PC17_99") (pintype "bidirectional"))
    )
    (net (code "79") (name "/PIN47") (class "Default")
      (node (ref "U1") (pin "98") (pinfunction "PC16_98") (pintype "bidirectional"))
    )
    (net (code "80") (name "/PIN48") (class "Default")
      (node (ref "U1") (pin "97") (pinfunction "PC15_97") (pintype "bidirectional"))
    )
    (net (code "81") (name "/PIN49") (class "Default")
      (node (ref "U1") (pin "96") (pinfunction "PC14_96") (pintype "bidirectional"))
    )
    (net (code "82") (name "/PIN50") (class "Default")
      (node (ref "U1") (pin "95") (pinfunction "PC13_95") (pintype "bidirectional"))
    )
    (net (code "83") (name "/PIN51") (class "Default")
      (node (ref "U1") (pin "94") (pinfunction "PC12_94") (pintype "bidirectional"))
    )
    (net (code "84") (name "/PWM2") (class "Default")
      (node (ref "SV1") (pin "5") (pinfunction "5_5") (pintype "passive"))
      (node (ref "U1") (pin "144") (pinfunction "PB25_144") (pintype "bidirectional"))
    )
    (net (code "85") (name "/PWM3") (class "Default")
      (node (ref "SV1") (pin "4") (pinfunction "4_4") (pintype "passive"))
      (node (ref "U1") (pin "139") (pinfunction "PC28_139") (pintype "bidirectional"))
    )
    (net (code "86") (name "/PWM5") (class "Default")
      (node (ref "SV1") (pin "2") (pinfunction "2_2") (pintype "passive"))
      (node (ref "U1") (pin "136") (pinfunction "PC25_136") (pintype "bidirectional"))
    )
    (net (code "87") (name "/PWM6") (class "Default")
      (node (ref "SV1") (pin "1") (pinfunction "1_1") (pintype "passive"))
      (node (ref "U1") (pin "135") (pinfunction "PC24_135") (pintype "bidirectional"))
    )
    (net (code "88") (name "/PWM7") (class "Default")
      (node (ref "U1") (pin "134") (pinfunction "PC23_134") (pintype "bidirectional"))
    )
    (net (code "89") (name "/PWM8") (class "Default")
      (node (ref "U1") (pin "133") (pinfunction "PC22_133") (pintype "bidirectional"))
    )
    (net (code "90") (name "/PWM9") (class "Default")
      (node (ref "U1") (pin "132") (pinfunction "PC21_132") (pintype "bidirectional"))
    )
    (net (code "91") (name "/PWM11") (class "Default")
      (node (ref "U1") (pin "20") (pinfunction "PD7_20") (pintype "bidirectional"))
    )
    (net (code "92") (name "/PWM12") (class "Default")
      (node (ref "U1") (pin "21") (pinfunction "PD8_21") (pintype "bidirectional"))
    )
    (net (code "93") (name "/PWM13") (class "Default")
      (node (ref "IC1") (pin "3") (pinfunction "+IN_3") (pintype "input"))
      (node (ref "U1") (pin "68") (pinfunction "PB27_68") (pintype "bidirectional"))
    )
    (net (code "94") (name "/RD+") (class "Default")
      (node (ref "IC6") (pin "29") (pinfunction "D+_29") (pintype "bidirectional"))
      (node (ref "R20") (pin "1") (pinfunction "1_1") (pintype "passive"))
    )
    (net (code "95") (name "/RD-") (class "Default")
      (node (ref "IC6") (pin "30") (pinfunction "D-_30") (pintype "bidirectional"))
      (node (ref "R19") (pin "1") (pinfunction "1_1") (pintype "passive"))
    )
    (net (code "96") (name "/RESET2") (class "Default")
      (node (ref "D2") (pin "A") (pinfunction "A_A") (pintype "passive"))
      (node (ref "IC6") (pin "24") (pinfunction "RESET(PC1/DW)_24") (pintype "input"))
      (node (ref "ICSP1") (pin "5") (pinfunction "5_5") (pintype "passive"))
      (node (ref "R13") (pin "1") (pinfunction "1_1") (pintype "passive"))
    )
    (net (code "97") (name "/RESET_CMD") (class "Default")
      (node (ref "IC6") (pin "22") (pinfunction "(INT4/ICP1/CLK0)PC7_22") (pintype "bidirectional"))
      (node (ref "R23") (pin "1") (pinfunction "1_1") (pintype "passive"))
    )
    (net (code "98") (name "/RX") (class "Default")
      (node (ref "IC10") (pin "4") (pinfunction "O_4") (pintype "tri_state"))
      (node (ref "U1") (pin "27") (pinfunction "PA8_27") (pintype "bidirectional"))
      (node (ref "U3") (pin "5") (pinfunction "RX_5") (pintype "bidirectional"))
      (node (ref "U3") (pin "6") (pinfunction "RX_6") (pintype "bidirectional"))
    )
    (net (code "99") (name "/RXD0") (class "Default")
      (node (ref "U1") (pin "18") (pinfunction "PD5_18") (pintype "bidirectional"))
    )
    (net (code "100") (name "/RXD1") (class "Default")
      (node (ref "U1") (pin "5") (pinfunction "PA12_5") (pintype "bidirectional"))
    )
    (net (code "101") (name "/RXD2") (class "Default")
      (node (ref "U1") (pin "3") (pinfunction "PA10_3") (pintype "bidirectional"))
    )
    (net (code "102") (name "/RXL") (class "Default")
      (node (ref "RX") (pin "C") (pinfunction "C_C") (pintype "passive"))
      (node (ref "U1") (pin "103") (pinfunction "PC30_103") (pintype "bidirectional"))
    )
    (net (code "103") (name "/RXL-U2") (class "Default")
      (node (ref "IC6") (pin "10") (pinfunction "(INT5/AIN3)PD4_10") (pintype "bidirectional"))
      (node (ref "RX1") (pin "C") (pinfunction "C_C") (pintype "passive"))
    )
    (net (code "104") (name "/SCK2") (class "Default")
      (node (ref "IC6") (pin "15") (pinfunction "(SCLK/PCINT1)PB1_15") (pintype "bidirectional"))
      (node (ref "ICSP1") (pin "3") (pinfunction "3_3") (pintype "passive"))
    )
    (net (code "105") (name "/SCL0-3") (class "Default")
      (node (ref "U1") (pin "87") (pinfunction "PB13_87") (pintype "bidirectional"))
    )
    (net (code "106") (name "/SCL1") (class "Default")
      (node (ref "U1") (pin "70") (pinfunction "PA18_70") (pintype "bidirectional"))
    )
    (net (code "107") (name "/SDA0-3") (class "Default")
      (node (ref "U1") (pin "86") (pinfunction "PB12_86") (pintype "bidirectional"))
    )
    (net (code "108") (name "/SDA1") (class "Default")
      (node (ref "U1") (pin "9") (pinfunction "PA17_9") (pintype "bidirectional"))
    )
    (net (code "109") (name "/SPCK") (class "Default")
      (node (ref "U1") (pin "110") (pinfunction "PA27_110") (pintype "bidirectional"))
    )
    (net (code "110") (name "/SS0{slash}PWM10") (class "Default")
      (node (ref "U1") (pin "102") (pinfunction "PC29_102") (pintype "bidirectional"))
      (node (ref "U1") (pin "111") (pinfunction "PA28_111") (pintype "bidirectional"))
    )
    (net (code "111") (name "/SS1{slash}PWM4") (class "Default")
      (node (ref "SV1") (pin "3") (pinfunction "3_3") (pintype "passive"))
      (node (ref "U1") (pin "112") (pinfunction "PA29_112") (pintype "bidirectional"))
      (node (ref "U1") (pin "137") (pinfunction "PC26_137") (pintype "bidirectional"))
    )
    (net (code "112") (name "/SS3") (class "Default")
      (node (ref "U1") (pin "142") (pinfunction "PB23_142") (pintype "bidirectional"))
    )
    (net (code "113") (name "/TX") (class "Default")
      (node (ref "IC6") (pin "8") (pinfunction "(RXD1/AIN1/INT2)PD2_8") (pintype "bidirectional"))
      (node (ref "U1") (pin "2") (pinfunction "PA9_2") (pintype "bidirectional"))
      (node (ref "U3") (pin "3") (pinfunction "TX_3") (pintype "bidirectional"))
      (node (ref "U3") (pin "8") (pinfunction "TX_8") (pintype "bidirectional"))
    )
    (net (code "114") (name "/TXD0") (class "Default")
      (node (ref "U1") (pin "17") (pinfunction "PD4_17") (pintype "bidirectional"))
    )
    (net (code "115") (name "/TXD1") (class "Default")
      (node (ref "U1") (pin "6") (pinfunction "PA13_6") (pintype "bidirectional"))
    )
    (net (code "116") (name "/TXD2") (class "Default")
      (node (ref "U1") (pin "4") (pinfunction "PA11_4") (pintype "bidirectional"))
    )
    (net (code "117") (name "/TXL") (class "Default")
      (node (ref "TX") (pin "C") (pinfunction "C_C") (pintype "passive"))
      (node (ref "U1") (pin "107") (pinfunction "PA21_107") (pintype "bidirectional"))
    )
    (net (code "118") (name "/TXL-U2") (class "Default")
      (node (ref "IC6") (pin "11") (pinfunction "(XCK/AIN4/PCINT12)PD5_11") (pintype "bidirectional"))
      (node (ref "TX1") (pin "C") (pinfunction "C_C") (pintype "passive"))
    )
    (net (code "119") (name "/UOTGID") (class "Default")
      (node (ref "U1") (pin "129") (pinfunction "PB11_129") (pintype "bidirectional"))
    )
    (net (code "120") (name "/UOTGVBOF") (class "Default")
      (node (ref "U1") (pin "128") (pinfunction "PB10_128") (pintype "bidirectional"))
    )
    (net (code "121") (name "/USBVCC") (class "Default")
      (node (ref "R21") (pin "2") (pinfunction "2_2") (pintype "passive"))
    )
    (net (code "122") (name "/USBVCCU2") (class "Default")
      (node (ref "C28") (pin "1") (pinfunction "1_1") (pintype "passive"))
      (node (ref "F2") (pin "1") (pinfunction "1_1") (pintype "passive"))
      (node (ref "IC6") (pin "31") (pinfunction "UVCC_31") (pintype "power_in"))
    )
    (net (code "123") (name "/VBG") (class "Default")
      (node (ref "C25") (pin "1") (pinfunction "1_1") (pintype "passive"))
      (node (ref "R7") (pin "2") (pinfunction "2_2") (pintype "passive"))
      (node (ref "U1") (pin "40") (pinfunction "VBG_40") (pintype "passive"))
    )
    (net (code "124") (name "/VDDANA") (class "Default")
      (node (ref "C10") (pin "2") (pinfunction "2_2") (pintype "passive"))
      (node (ref "C3") (pin "+") (pinfunction "+_+") (pintype "passive"))
      (node (ref "L1") (pin "2") (pinfunction "2_2") (pintype "passive"))
      (node (ref "U1") (pin "73") (pinfunction "VDDANA_73") (pintype "power_in"))
    )
    (net (code "125") (name "/VDDOUT") (class "Default")
      (node (ref "C11") (pin "+") (pinfunction "+_+") (pintype "passive"))
      (node (ref "C12") (pin "2") (pinfunction "2_2") (pintype "passive"))
      (node (ref "C13") (pin "2") (pinfunction "2_2") (pintype "passive"))
      (node (ref "C14") (pin "2") (pinfunction "2_2") (pintype "passive"))
      (node (ref "C15") (pin "2") (pinfunction "2_2") (pintype "passive"))
      (node (ref "C16") (pin "2") (pinfunction "2_2") (pintype "passive"))
      (node (ref "C17") (pin "2") (pinfunction "2_2") (pintype "passive"))
      (node (ref "L5") (pin "1") (pinfunction "1_1") (pintype "passive"))
      (node (ref "U1") (pin "10") (pinfunction "VDDCORE1_10") (pintype "input"))
      (node (ref "U1") (pin "104") (pinfunction "VDDCORE4_104") (pintype "input"))
      (node (ref "U1") (pin "124") (pinfunction "VDDCORE5_124") (pintype "input"))
      (node (ref "U1") (pin "45") (pinfunction "VDDCORE2_45") (pintype "input"))
      (node (ref "U1") (pin "56") (pinfunction "VDDOUT_56") (pintype "output"))
      (node (ref "U1") (pin "61") (pinfunction "VDDCORE3_61") (pintype "input"))
    )
    (net (code "126") (name "/VDDOUTMI") (class "Default")
      (node (ref "C2") (pin "+") (pinfunction "+_+") (pintype "passive"))
      (node (ref "C9") (pin "2") (pinfunction "2_2") (pintype "passive"))
      (node (ref "L2") (pin "2") (pinfunction "2_2") (pintype "passive"))
      (node (ref "U1") (pin "41") (pinfunction "VDDUTMI_41") (pintype "input"))
    )
    (net (code "127") (name "/VDDPLL") (class "Default")
      (node (ref "C32") (pin "2") (pinfunction "2_2") (pintype "passive"))
      (node (ref "C33") (pin "+") (pinfunction "+_+") (pintype "passive"))
      (node (ref "L5") (pin "2") (pinfunction "2_2") (pintype "passive"))
      (node (ref "U1") (pin "34") (pinfunction "VDDPLL_34") (pintype "input"))
    )
    (net (code "128") (name "/VUCAP") (class "Default")
      (node (ref "C38") (pin "1") (pinfunction "1_1") (pintype "passive"))
      (node (ref "IC6") (pin "27") (pinfunction "UCAP_27") (pintype "passive"))
    )
    (net (code "129") (name "/XIN") (class "Default")
      (node (ref "C22") (pin "1") (pinfunction "1_1") (pintype "passive"))
      (node (ref "U1") (pin "36") (pinfunction "XIN_36") (pintype "input"))
      (node (ref "Y1") (pin "1") (pinfunction "C1_1") (pintype "passive"))
    )
    (net (code "130") (name "/XIN32") (class "Default")
      (node (ref "C24") (pin "1") (pinfunction "1_1") (pintype "passive"))
      (node (ref "U1") (pin "48") (pinfunction "XIN32_48") (pintype "output"))
      (node (ref "Y2") (pin "P$2") (pinfunction "2_P$2") (pintype "bidirectional"))
    )
    (net (code "131") (name "/XOUT") (class "Default")
      (node (ref "C21") (pin "1") (pinfunction "1_1") (pintype "passive"))
      (node (ref "U1") (pin "35") (pinfunction "XOUT_35") (pintype "output"))
      (node (ref "Y1") (pin "3") (pinfunction "C2_3") (pintype "passive"))
    )
    (net (code "132") (name "/XOUT32") (class "Default")
      (node (ref "C23") (pin "1") (pinfunction "1_1") (pintype "passive"))
      (node (ref "U1") (pin "49") (pinfunction "XOUT32_49") (pintype "output"))
      (node (ref "Y2") (pin "P$1") (pinfunction "1_P$1") (pintype "bidirectional"))
    )
    (net (code "133") (name "/XT1") (class "Default")
      (node (ref "C39") (pin "1") (pinfunction "1_1") (pintype "passive"))
      (node (ref "IC6") (pin "1") (pinfunction "XTAL1_1") (pintype "bidirectional"))
      (node (ref "R9") (pin "1") (pinfunction "1_1") (pintype "passive"))
      (node (ref "Y4") (pin "1") (pinfunction "C1_1") (pintype "passive"))
    )
    (net (code "134") (name "/XT2") (class "Default")
      (node (ref "C40") (pin "1") (pinfunction "1_1") (pintype "passive"))
      (node (ref "IC6") (pin "2") (pinfunction "XTAL2(PC0)_2") (pintype "bidirectional"))
      (node (ref "R9") (pin "2") (pinfunction "2_2") (pintype "passive"))
      (node (ref "Y4") (pin "3") (pinfunction "C2_3") (pintype "passive"))
    )
    (net (code "135") (name "/XVCC") (class "Default")
      (node (ref "F2") (pin "2") (pinfunction "2_2") (pintype "passive"))
      (node (ref "J3") (pin "P1") (pinfunction "VBUS_P1") (pintype "power_in"))
    )
    (net (code "136") (name "GND") (class "Default")
      (node (ref "C1") (pin "-") (pinfunction "-_-") (pintype "passive"))
      (node (ref "C10") (pin "1") (pinfunction "1_1") (pintype "passive"))
      (node (ref "C11") (pin "-") (pinfunction "-_-") (pintype "passive"))
      (node (ref "C12") (pin "1") (pinfunction "1_1") (pintype "passive"))
      (node (ref "C13") (pin "1") (pinfunction "1_1") (pintype "passive"))
      (node (ref "C14") (pin "1") (pinfunction "1_1") (pintype "passive"))
      (node (ref "C15") (pin "1") (pinfunction "1_1") (pintype "passive"))
      (node (ref "C16") (pin "1") (pinfunction "1_1") (pintype "passive"))
      (node (ref "C17") (pin "1") (pinfunction "1_1") (pintype "passive"))
      (node (ref "C18") (pin "1") (pinfunction "1_1") (pintype "passive"))
      (node (ref "C19") (pin "1") (pinfunction "1_1") (pintype "passive"))
      (node (ref "C2") (pin "-") (pinfunction "-_-") (pintype "passive"))
      (node (ref "C21") (pin "2") (pinfunction "2_2") (pintype "passive"))
      (node (ref "C22") (pin "2") (pinfunction "2_2") (pintype "passive"))
      (node (ref "C23") (pin "2") (pinfunction "2_2") (pintype "passive"))
      (node (ref "C24") (pin "2") (pinfunction "2_2") (pintype "passive"))
      (node (ref "C25") (pin "2") (pinfunction "2_2") (pintype "passive"))
      (node (ref "C28") (pin "2") (pinfunction "2_2") (pintype "passive"))
      (node (ref "C29") (pin "-") (pinfunction "-_-") (pintype "passive"))
      (node (ref "C3") (pin "-") (pinfunction "-_-") (pintype "passive"))
      (node (ref "C30") (pin "1") (pinfunction "1_1") (pintype "passive"))
      (node (ref "C32") (pin "1") (pinfunction "1_1") (pintype "passive"))
      (node (ref "C33") (pin "-") (pinfunction "-_-") (pintype "passive"))
      (node (ref "C34") (pin "1") (pinfunction "1_1") (pintype "passive"))
      (node (ref "C36") (pin "2") (pinfunction "2_2") (pintype "passive"))
      (node (ref "C37") (pin "2") (pinfunction "2_2") (pintype "passive"))
      (node (ref "C38") (pin "2") (pinfunction "2_2") (pintype "passive"))
      (node (ref "C39") (pin "2") (pinfunction "2_2") (pintype "passive"))
      (node (ref "C4") (pin "1") (pinfunction "1_1") (pintype "passive"))
      (node (ref "C40") (pin "2") (pinfunction "2_2") (pintype "passive"))
      (node (ref "C43") (pin "-") (pinfunction "-_-") (pintype "passive"))
      (node (ref "C44") (pin "-") (pinfunction "-_-") (pintype "passive"))
      (node (ref "C5") (pin "1") (pinfunction "1_1") (pintype "passive"))
      (node (ref "C6") (pin "1") (pinfunction "1_1") (pintype "passive"))
      (node (ref "C7") (pin "1") (pinfunction "1_1") (pintype "passive"))
      (node (ref "C8") (pin "1") (pinfunction "1_1") (pintype "passive"))
      (node (ref "C9") (pin "1") (pinfunction "1_1") (pintype "passive"))
      (node (ref "GND_IN") (pin "TP") (pinfunction "TP_TP") (pintype "input"))
      (node (ref "IC1") (pin "4") (pinfunction "V-_4") (pintype "power_in"))
      (node (ref "IC10") (pin "3") (pinfunction "GND_3") (pintype "power_in"))
      (node (ref "IC4") (pin "1") (pinfunction "GND/ADJ_1") (pintype "input"))
      (node (ref "IC6") (pin "28") (pinfunction "UGND_28") (pintype "power_in"))
      (node (ref "IC6") (pin "3") (pinfunction "GND_3") (pintype "power_in"))
      (node (ref "IC6") (pin "33") (pinfunction "PAD_33") (pintype "power_in"))
      (node (ref "ICSP1") (pin "6") (pinfunction "6_6") (pintype "passive"))
      (node (ref "J3") (pin "P$1") (pinfunction "SH7_P$1") (pintype "passive"))
      (node (ref "J3") (pin "P$2") (pinfunction "SH8_P$2") (pintype "passive"))
      (node (ref "J3") (pin "P$3") (pinfunction "SH9_P$3") (pintype "passive"))
      (node (ref "J3") (pin "P$4") (pinfunction "SH10_P$4") (pintype "passive"))
      (node (ref "J3") (pin "P$5") (pinfunction "SH11_P$5") (pintype "passive"))
      (node (ref "J3") (pin "P$6") (pinfunction "SH12_P$6") (pintype "passive"))
      (node (ref "J3") (pin "P$7") (pinfunction "SH13_P$7") (pintype "passive"))
      (node (ref "J3") (pin "P$8") (pinfunction "SH14_P$8") (pintype "passive"))
      (node (ref "J3") (pin "P5") (pinfunction "GND_P5") (pintype "passive"))
      (node (ref "J3") (pin "S1") (pinfunction "SH1_S1") (pintype "passive"))
      (node (ref "J3") (pin "S2") (pinfunction "SH2_S2") (pintype "passive"))
      (node (ref "J3") (pin "S3") (pinfunction "SH3_S3") (pintype "passive"))
      (node (ref "J3") (pin "S4") (pinfunction "SH4_S4") (pintype "passive"))
      (node (ref "J3") (pin "S5") (pinfunction "SH5_S5") (pintype "passive"))
      (node (ref "J3") (pin "S6") (pinfunction "SH6_S6") (pintype "passive"))
      (node (ref "JTAG") (pin "3") (pinfunction "3_3") (pintype "passive"))
      (node (ref "JTAG") (pin "5") (pinfunction "5_5") (pintype "passive"))
      (node (ref "JTAG") (pin "9") (pinfunction "9_9") (pintype "passive"))
      (node (ref "L") (pin "C") (pinfunction "C_C") (pintype "passive"))
      (node (ref "ON") (pin "C") (pinfunction "C_C") (pintype "passive"))
      (node (ref "R17") (pin "1") (pinfunction "1_1") (pintype "passive"))
      (node (ref "R18") (pin "2") (pinfunction "2_2") (pintype "passive"))
      (node (ref "R24") (pin "1") (pinfunction "1_1") (pintype "passive"))
      (node (ref "R26") (pin "1") (pinfunction "1_1") (pintype "passive"))
      (node (ref "R7") (pin "1") (pinfunction "1_1") (pintype "passive"))
      (node (ref "R8") (pin "1") (pinfunction "1_1") (pintype "passive"))
      (node (ref "RN1") (pin "1") (pinfunction "1_1") (pintype "passive"))
      (node (ref "RN1") (pin "2") (pinfunction "1_2") (pintype "passive"))
      (node (ref "RN1") (pin "7") (pinfunction "2_7") (pintype "passive"))
      (node (ref "RN1") (pin "8") (pinfunction "2_8") (pintype "passive"))
      (node (ref "RN2") (pin "1") (pinfunction "1_1") (pintype "passive"))
      (node (ref "RN2") (pin "4") (pinfunction "1_4") (pintype "passive"))
      (node (ref "RN2") (pin "5") (pinfunction "2_5") (pintype "passive"))
      (node (ref "RN2") (pin "8") (pinfunction "2_8") (pintype "passive"))
      (node (ref "SV3") (pin "1") (pinfunction "1_1") (pintype "passive"))
      (node (ref "SV3") (pin "2") (pinfunction "2_2") (pintype "passive"))
      (node (ref "T5") (pin "TP") (pinfunction "TP_TP") (pintype "input"))
      (node (ref "T6") (pin "TP") (pinfunction "TP_TP") (pintype "input"))
      (node (ref "T7") (pin "TP") (pinfunction "TP_TP") (pintype "input"))
      (node (ref "U$1") (pin "3") (pinfunction "GND_3") (pintype "bidirectional"))
      (node (ref "U$1") (pin "6") (pinfunction "GND_6") (pintype "bidirectional"))
      (node (ref "U1") (pin "106") (pinfunction "GND3_106") (pintype "power_in"))
      (node (ref "U1") (pin "12") (pinfunction "GND1_12") (pintype "power_in"))
      (node (ref "U1") (pin "126") (pinfunction "GND4_126") (pintype "power_in"))
      (node (ref "U1") (pin "33") (pinfunction "GNDPLL_33") (pintype "power_in"))
      (node (ref "U1") (pin "44") (pinfunction "GNDUTMI_44") (pintype "power_in"))
      (node (ref "U1") (pin "46") (pinfunction "JTAGSEL_46") (pintype "input"))
      (node (ref "U1") (pin "54") (pinfunction "GNDBU_54") (pintype "power_in"))
      (node (ref "U1") (pin "58") (pinfunction "GND2_58") (pintype "power_in"))
      (node (ref "U1") (pin "74") (pinfunction "GNDANA_74") (pintype "power_in"))
      (node (ref "U2") (pin "2") (pinfunction "VSS_2") (pintype "bidirectional"))
      (node (ref "U2") (pin "8") (pinfunction "RS_8") (pintype "bidirectional"))
      (node (ref "U3") (pin "4") (pinfunction "GND_4") (pintype "bidirectional"))
      (node (ref "U3") (pin "7") (pinfunction "GND_7") (pintype "bidirectional"))
      (node (ref "U4") (pin "2") (pinfunction "VSS_2") (pintype "bidirectional"))
      (node (ref "U4") (pin "8") (pinfunction "RS_8") (pintype "bidirectional"))
      (node (ref "Y1") (pin "2") (pinfunction "GND_2") (pintype "passive"))
      (node (ref "Y1") (pin "4") (pinfunction "GND_4") (pintype "passive"))
      (node (ref "Y4") (pin "2") (pinfunction "GND_2") (pintype "passive"))
      (node (ref "Y4") (pin "4") (pinfunction "GND_4") (pintype "passive"))
      (node (ref "Z3") (pin "1") (pinfunction "1_1") (pintype "passive"))
      (node (ref "Z4") (pin "1") (pinfunction "1_1") (pintype "passive"))
    )
    (net (code "137") (name "Net-(BR1-C)") (class "Default")
      (node (ref "BR1") (pin "2") (pinfunction "C_2") (pintype "passive"))
      (node (ref "C34") (pin "2") (pinfunction "2_2") (pintype "passive"))
      (node (ref "JR1") (pin "2") (pinfunction "2_2") (pintype "passive"))
      (node (ref "L3") (pin "1") (pinfunction "1_1") (pintype "passive"))
    )
    (net (code "138") (name "Net-(IC6-(CTS{slash}HWB{slash}AIN6{slash}TO{slash}INT7)PD7)") (class "Default")
      (node (ref "IC6") (pin "13") (pinfunction "(CTS/HWB/AIN6/TO/INT7)PD7_13") (pintype "bidirectional"))
      (node (ref "R18") (pin "1") (pinfunction "1_1") (pintype "passive"))
    )
    (net (code "139") (name "Net-(R14-Pad2)") (class "Default")
      (node (ref "R14") (pin "2") (pinfunction "2_2") (pintype "passive"))
      (node (ref "TX1") (pin "A") (pinfunction "A_A") (pintype "passive"))
    )
    (net (code "140") (name "Net-(R15-Pad2)") (class "Default")
      (node (ref "R15") (pin "2") (pinfunction "2_2") (pintype "passive"))
      (node (ref "RX1") (pin "A") (pinfunction "A_A") (pintype "passive"))
    )
    (net (code "141") (name "Net-(RES-PadTP)") (class "Default")
      (node (ref "RES") (pin "TP") (pinfunction "TP_TP") (pintype "input"))
      (node (ref "U3") (pin "2") (pinfunction "RES_2") (pintype "bidirectional"))
      (node (ref "U3") (pin "9") (pinfunction "RES_9") (pintype "bidirectional"))
    )
    (net (code "142") (name "Net-(RN3-Pad1)") (class "Default")
      (node (ref "RN3") (pin "1") (pinfunction "1_1") (pintype "passive"))
      (node (ref "RX") (pin "A") (pinfunction "A_A") (pintype "passive"))
    )
    (net (code "143") (name "Net-(RN3B-1)") (class "Default")
      (node (ref "RN3") (pin "2") (pinfunction "1_2") (pintype "passive"))
      (node (ref "TX") (pin "A") (pinfunction "A_A") (pintype "passive"))
    )
    (net (code "144") (name "Net-(RN3C-1)") (class "Default")
      (node (ref "L") (pin "A") (pinfunction "A_A") (pintype "passive"))
      (node (ref "RN3") (pin "3") (pinfunction "1_3") (pintype "passive"))
    )
    (net (code "145") (name "Net-(RN3D-1)") (class "Default")
      (node (ref "ON") (pin "A") (pinfunction "A_A") (pintype "passive"))
      (node (ref "RN3") (pin "4") (pinfunction "1_4") (pintype "passive"))
    )
    (net (code "146") (name "Net-(U$1-EN)") (class "Default")
      (node (ref "+12V_IN") (pin "TP") (pinfunction "TP_TP") (pintype "input"))
      (node (ref "C43") (pin "+") (pinfunction "+_+") (pintype "passive"))
      (node (ref "U$1") (pin "1") (pinfunction "EN_1") (pintype "bidirectional"))
      (node (ref "U$1") (pin "2") (pinfunction "VIN_2") (pintype "bidirectional"))
    )
    (net (code "147") (name "Net-(U$1-VADJ)") (class "Default")
      (node (ref "R16") (pin "1") (pinfunction "1_1") (pintype "passive"))
      (node (ref "R17") (pin "2") (pinfunction "2_2") (pintype "passive"))
      (node (ref "U$1") (pin "5") (pinfunction "VADJ_5") (pintype "bidirectional"))
    )
    (net (code "148") (name "Net-(U1-DFSDM)") (class "Default")
      (node (ref "R5") (pin "2") (pinfunction "2_2") (pintype "passive"))
      (node (ref "U1") (pin "43") (pinfunction "DFSDM_43") (pintype "input"))
    )
    (net (code "149") (name "Net-(U1-DFSDP)") (class "Default")
      (node (ref "R6") (pin "2") (pinfunction "2_2") (pintype "passive"))
      (node (ref "U1") (pin "42") (pinfunction "DFSDP_42") (pintype "input"))
    )
    (net (code "150") (name "Net-(U1-FWUP)") (class "Default")
      (node (ref "R4") (pin "1") (pinfunction "1_1") (pintype "passive"))
      (node (ref "U1") (pin "53") (pinfunction "FWUP_53") (pintype "input"))
    )
    (net (code "151") (name "Net-(U1-TST)") (class "Default")
      (node (ref "R8") (pin "2") (pinfunction "2_2") (pintype "passive"))
      (node (ref "U1") (pin "51") (pinfunction "TST_51") (pintype "input"))
    )
    (net (code "152") (name "Net-(U2-CANH)") (class "Default")
      (node (ref "CANH_1") (pin "TP") (pinfunction "TP_TP") (pintype "input"))
      (node (ref "R28") (pin "2") (pinfunction "2_2") (pintype "passive"))
      (node (ref "U2") (pin "7") (pinfunction "CANH_7") (pintype "bidirectional"))
    )
    (net (code "153") (name "Net-(U2-CANL)") (class "Default")
      (node (ref "CANL_1") (pin "TP") (pinfunction "TP_TP") (pintype "input"))
      (node (ref "R28") (pin "1") (pinfunction "1_1") (pintype "passive"))
      (node (ref "U2") (pin "6") (pinfunction "CANL_6") (pintype "bidirectional"))
    )
    (net (code "154") (name "Net-(U2-VREF)") (class "Default")
      (node (ref "R26") (pin "2") (pinfunction "2_2") (pintype "passive"))
      (node (ref "R27") (pin "1") (pinfunction "1_1") (pintype "passive"))
      (node (ref "U2") (pin "5") (pinfunction "VREF_5") (pintype "bidirectional"))
    )
    (net (code "155") (name "Net-(U4-CANH)") (class "Default")
      (node (ref "CANH_0") (pin "TP") (pinfunction "TP_TP") (pintype "input"))
      (node (ref "R25") (pin "2") (pinfunction "2_2") (pintype "passive"))
      (node (ref "U4") (pin "7") (pinfunction "CANH_7") (pintype "bidirectional"))
    )
    (net (code "156") (name "Net-(U4-CANL)") (class "Default")
      (node (ref "CANL_0") (pin "TP") (pinfunction "TP_TP") (pintype "input"))
      (node (ref "R25") (pin "1") (pinfunction "1_1") (pintype "passive"))
      (node (ref "U4") (pin "6") (pinfunction "CANL_6") (pintype "bidirectional"))
    )
    (net (code "157") (name "Net-(U4-VREF)") (class "Default")
      (node (ref "R22") (pin "1") (pinfunction "1_1") (pintype "passive"))
      (node (ref "R24") (pin "2") (pinfunction "2_2") (pintype "passive"))
      (node (ref "U4") (pin "5") (pinfunction "VREF_5") (pintype "bidirectional"))
    )
    (net (code "158") (name "XUSB") (class "Default")
      (node (ref "U1") (pin "39") (pinfunction "VBUS_39") (pintype "power_in"))
    )
    (net (code "159") (name "unconnected-(IC6-(AIN0{slash}INT1)PD1-Pad7)") (class "Default")
      (node (ref "IC6") (pin "7") (pinfunction "(AIN0/INT1)PD1_7") (pintype "bidirectional"))
    )
    (net (code "160") (name "unconnected-(IC6-(AIN2{slash}PCINT11)PC2-Pad5)") (class "Default")
      (node (ref "IC6") (pin "5") (pinfunction "(AIN2/PCINT11)PC2_5") (pintype "bidirectional"))
    )
    (net (code "161") (name "unconnected-(IC6-(OC0B{slash}INT0)PD0-Pad6)") (class "Default")
      (node (ref "IC6") (pin "6") (pinfunction "(OC0B/INT0)PD0_6") (pintype "bidirectional"))
    )
    (net (code "162") (name "unconnected-(IC6-(PCINT5)PB5-Pad19)") (class "Default")
      (node (ref "IC6") (pin "19") (pinfunction "(PCINT5)PB5_19") (pintype "bidirectional"))
    )
    (net (code "163") (name "unconnected-(IC6-(PCINT6)PB6-Pad20)") (class "Default")
      (node (ref "IC6") (pin "20") (pinfunction "(PCINT6)PB6_20") (pintype "bidirectional"))
    )
    (net (code "164") (name "unconnected-(IC6-(PCINT7{slash}OC0A{slash}OC1C)PB7-Pad21)") (class "Default")
      (node (ref "IC6") (pin "21") (pinfunction "(PCINT7/OC0A/OC1C)PB7_21") (pintype "bidirectional"))
    )
    (net (code "165") (name "unconnected-(IC6-(PCINT9{slash}OC1B)PC5-Pad25)") (class "Default")
      (node (ref "IC6") (pin "25") (pinfunction "(PCINT9/OC1B)PC5_25") (pintype "bidirectional"))
    )
    (net (code "166") (name "unconnected-(IC6-(RTS{slash}AIN5{slash}INT6)PD6-Pad12)") (class "Default")
      (node (ref "IC6") (pin "12") (pinfunction "(RTS/AIN5/INT6)PD6_12") (pintype "bidirectional"))
    )
    (net (code "167") (name "unconnected-(IC6-(SS{slash}PCINT0)PB0-Pad14)") (class "Default")
      (node (ref "IC6") (pin "14") (pinfunction "(SS/PCINT0)PB0_14") (pintype "bidirectional"))
    )
    (net (code "168") (name "unconnected-(IC6-(T1{slash}PCINT4)PB4-Pad18)") (class "Default")
      (node (ref "IC6") (pin "18") (pinfunction "(T1/PCINT4)PB4_18") (pintype "bidirectional"))
    )
    (net (code "169") (name "unconnected-(J3-ID-PadP4)") (class "Default")
      (node (ref "J3") (pin "P4") (pinfunction "ID_P4") (pintype "bidirectional"))
    )
    (net (code "170") (name "unconnected-(JTAG-Pad7)") (class "Default")
      (node (ref "JTAG") (pin "7") (pinfunction "7_7") (pintype "passive"))
    )
    (net (code "171") (name "unconnected-(U1-NRST-Pad69)") (class "Default")
      (node (ref "U1") (pin "69") (pinfunction "NRST_69") (pintype "bidirectional"))
    )
    (net (code "172") (name "unconnected-(U1-PB22-Pad141)") (class "Default")
      (node (ref "U1") (pin "141") (pinfunction "PB22_141") (pintype "bidirectional"))
    )
    (net (code "173") (name "unconnected-(U1-PB24-Pad143)") (class "Default")
      (node (ref "U1") (pin "143") (pinfunction "PB24_143") (pintype "bidirectional"))
    )
    (net (code "174") (name "unconnected-(U1-PC0-Pad130)") (class "Default")
      (node (ref "U1") (pin "130") (pinfunction "PC0_130") (pintype "bidirectional"))
    )
    (net (code "175") (name "unconnected-(U1-PC10-Pad117)") (class "Default")
      (node (ref "U1") (pin "117") (pinfunction "PC10_117") (pintype "bidirectional"))
    )
    (net (code "176") (name "unconnected-(U1-PC11-Pad93)") (class "Default")
      (node (ref "U1") (pin "93") (pinfunction "PC11_93") (pintype "bidirectional"))
    )
    (net (code "177") (name "unconnected-(U1-PC20-Pad131)") (class "Default")
      (node (ref "U1") (pin "131") (pinfunction "PC20_131") (pintype "bidirectional"))
    )
    (net (code "178") (name "unconnected-(U1-PC27-Pad138)") (class "Default")
      (node (ref "U1") (pin "138") (pinfunction "PC27_138") (pintype "bidirectional"))
    )
    (net (code "179") (name "unconnected-(U1-SHDN-Pad50)") (class "Default")
      (node (ref "U1") (pin "50") (pinfunction "SHDN_50") (pintype "output"))
    )
  )
)
